# main.net
KiCad netlist of a schematic drawn in EAGLE
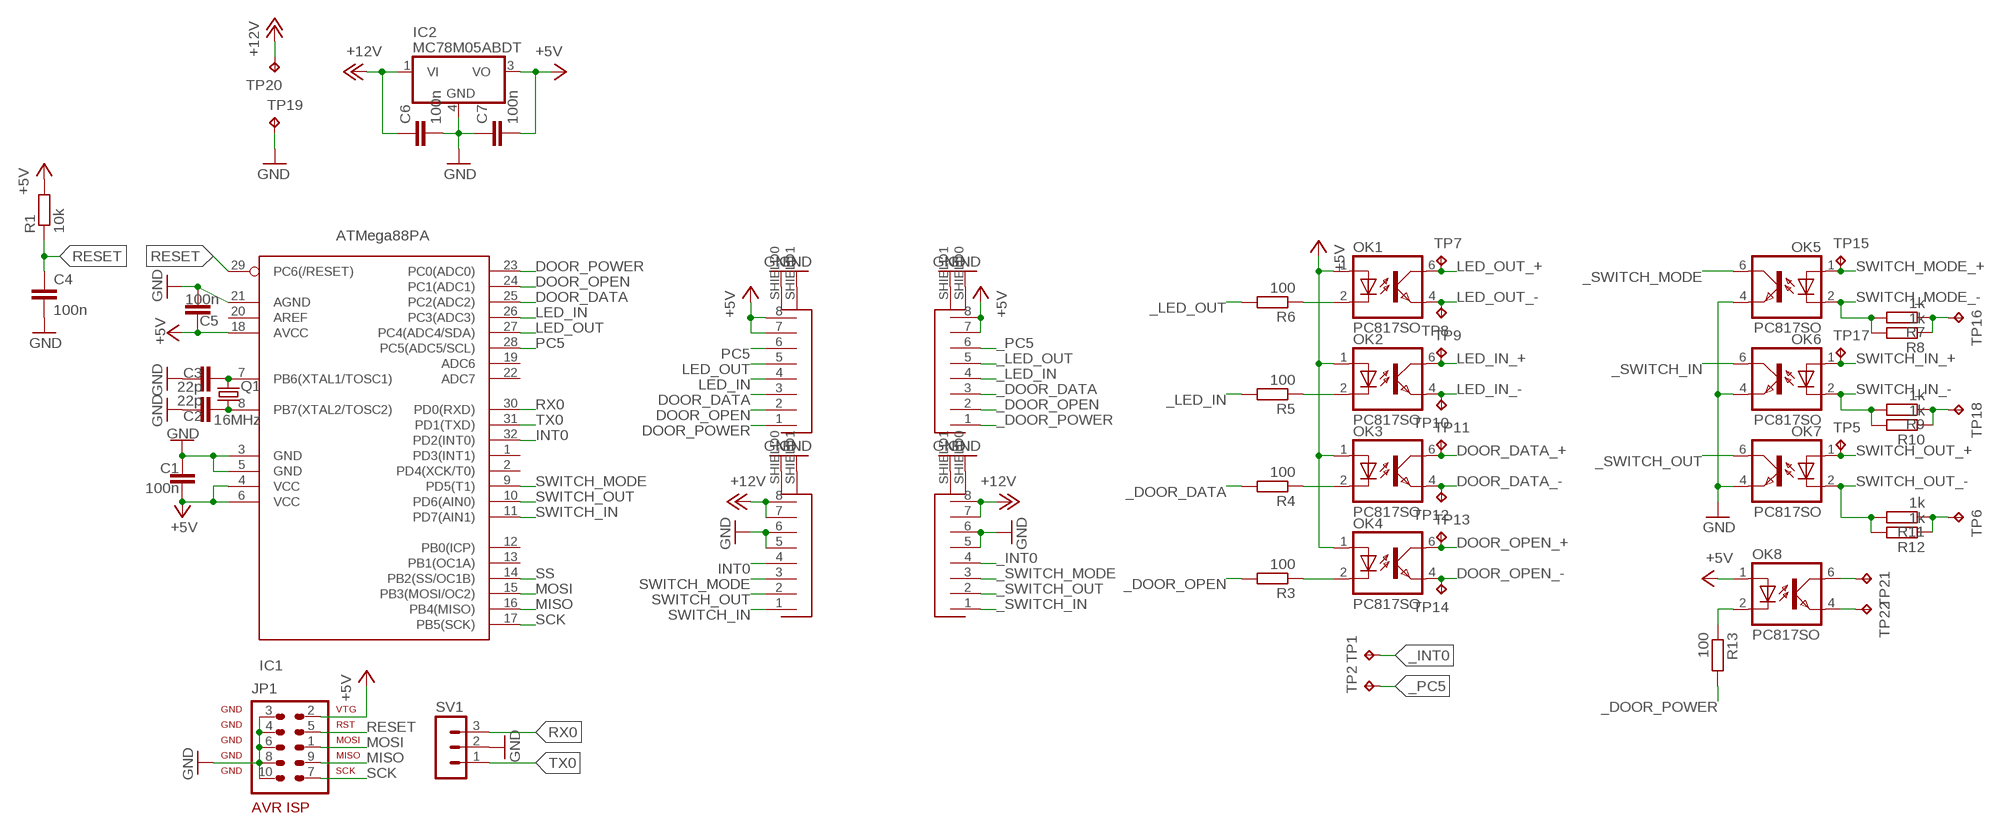
[diagram p0: schematic, sheet 1]

(export (version "E")
  (design (tool "Eeschema 10.0.6"))
  (components
    (comp (ref "C1")
      (value "100n")
      (footprint "eagle-import:C0805")
      (libsource (lib "eagle-import") (part "C-EUC0805"))
    )
    (comp (ref "C2")
      (value "22p")
      (footprint "eagle-import:C0805")
      (libsource (lib "eagle-import") (part "C-EUC0805"))
    )
    (comp (ref "C3")
      (value "22p")
      (footprint "eagle-import:C0805")
      (libsource (lib "eagle-import") (part "C-EUC0805"))
    )
    (comp (ref "C4")
      (value "100n")
      (footprint "eagle-import:C0805")
      (libsource (lib "eagle-import") (part "C-EUC0805"))
    )
    (comp (ref "C5")
      (value "100n")
      (footprint "eagle-import:C0805")
      (libsource (lib "eagle-import") (part "C-EUC0805"))
    )
    (comp (ref "C6")
      (value "100n")
      (footprint "eagle-import:C0805")
      (libsource (lib "eagle-import") (part "C-EUC0805"))
    )
    (comp (ref "C7")
      (value "100n")
      (footprint "eagle-import:C0805")
      (libsource (lib "eagle-import") (part "C-EUC0805"))
    )
    (comp (ref "CON1")
      (value "451000")
      (footprint "eagle-import:451000")
      (libsource (lib "eagle-import") (part "451000"))
    )
    (comp (ref "CON1_")
      (value "451000")
      (footprint "eagle-import:451000")
      (libsource (lib "eagle-import") (part "451000"))
    )
    (comp (ref "CON2")
      (value "451000")
      (footprint "eagle-import:451000")
      (libsource (lib "eagle-import") (part "451000"))
    )
    (comp (ref "CON2_")
      (value "451000")
      (footprint "eagle-import:451000")
      (libsource (lib "eagle-import") (part "451000"))
    )
    (comp (ref "IC1")
      (value "ATMega88PA")
      (footprint "eagle-import:TQFP32-08")
      (libsource (lib "eagle-import") (part "MEGA8-AI"))
    )
    (comp (ref "IC2")
      (value "MC78M05ABDT")
      (footprint "eagle-import:DPACK_3")
      (libsource (lib "eagle-import") (part "MC78M05ABDT"))
    )
    (comp (ref "JP1")
      (value "AVR-ISP-10")
      (footprint "eagle-import:AVR-ISP-10")
      (libsource (lib "eagle-import") (part "AVR-ISP-10"))
    )
    (comp (ref "OK1")
      (value "PC817SO")
      (footprint "eagle-import:SO4")
      (libsource (lib "eagle-import") (part "PC817SO"))
    )
    (comp (ref "OK2")
      (value "PC817SO")
      (footprint "eagle-import:SO4")
      (libsource (lib "eagle-import") (part "PC817SO"))
    )
    (comp (ref "OK3")
      (value "PC817SO")
      (footprint "eagle-import:SO4")
      (libsource (lib "eagle-import") (part "PC817SO"))
    )
    (comp (ref "OK4")
      (value "PC817SO")
      (footprint "eagle-import:SO4")
      (libsource (lib "eagle-import") (part "PC817SO"))
    )
    (comp (ref "OK5")
      (value "PC817SO")
      (footprint "eagle-import:SO4")
      (libsource (lib "eagle-import") (part "PC817SO"))
    )
    (comp (ref "OK6")
      (value "PC817SO")
      (footprint "eagle-import:SO4")
      (libsource (lib "eagle-import") (part "PC817SO"))
    )
    (comp (ref "OK7")
      (value "PC817SO")
      (footprint "eagle-import:SO4")
      (libsource (lib "eagle-import") (part "PC817SO"))
    )
    (comp (ref "OK8")
      (value "PC817SO")
      (footprint "eagle-import:SO4")
      (libsource (lib "eagle-import") (part "PC817SO"))
    )
    (comp (ref "Q1")
      (value "16MHz")
      (footprint "eagle-import:MQ")
      (libsource (lib "eagle-import") (part "CRYSTALMQ"))
    )
    (comp (ref "R1")
      (value "10k")
      (footprint "eagle-import:M0805")
      (libsource (lib "eagle-import") (part "R-EU_M0805"))
    )
    (comp (ref "R3")
      (value "100")
      (footprint "eagle-import:M0805")
      (libsource (lib "eagle-import") (part "R-EU_M0805"))
    )
    (comp (ref "R4")
      (value "100")
      (footprint "eagle-import:M0805")
      (libsource (lib "eagle-import") (part "R-EU_M0805"))
    )
    (comp (ref "R5")
      (value "100")
      (footprint "eagle-import:M0805")
      (libsource (lib "eagle-import") (part "R-EU_M0805"))
    )
    (comp (ref "R6")
      (value "100")
      (footprint "eagle-import:M0805")
      (libsource (lib "eagle-import") (part "R-EU_M0805"))
    )
    (comp (ref "R7")
      (value "1k")
      (footprint "eagle-import:M0805")
      (libsource (lib "eagle-import") (part "R-EU_M0805"))
    )
    (comp (ref "R8")
      (value "1k")
      (footprint "eagle-import:M0805")
      (libsource (lib "eagle-import") (part "R-EU_M0805"))
    )
    (comp (ref "R9")
      (value "1k")
      (footprint "eagle-import:M0805")
      (libsource (lib "eagle-import") (part "R-EU_M0805"))
    )
    (comp (ref "R10")
      (value "1k")
      (footprint "eagle-import:M0805")
      (libsource (lib "eagle-import") (part "R-EU_M0805"))
    )
    (comp (ref "R11")
      (value "1k")
      (footprint "eagle-import:M0805")
      (libsource (lib "eagle-import") (part "R-EU_M0805"))
    )
    (comp (ref "R12")
      (value "1k")
      (footprint "eagle-import:M0805")
      (libsource (lib "eagle-import") (part "R-EU_M0805"))
    )
    (comp (ref "R13")
      (value "100")
      (footprint "eagle-import:M0805")
      (libsource (lib "eagle-import") (part "R-EU_M0805"))
    )
    (comp (ref "SV1")
      (value "MA03-1")
      (footprint "eagle-import:MA03-1")
      (libsource (lib "eagle-import") (part "MA03-1"))
    )
    (comp (ref "TP1")
      (value "TPTP20SQ")
      (footprint "eagle-import:TP20SQ")
      (libsource (lib "eagle-import") (part "TPTP20SQ"))
    )
    (comp (ref "TP2")
      (value "TPTP20SQ")
      (footprint "eagle-import:TP20SQ")
      (libsource (lib "eagle-import") (part "TPTP20SQ"))
    )
    (comp (ref "TP5")
      (value "TPTP20SQ")
      (footprint "eagle-import:TP20SQ")
      (libsource (lib "eagle-import") (part "TPTP20SQ"))
    )
    (comp (ref "TP6")
      (value "TPTP20SQ")
      (footprint "eagle-import:TP20SQ")
      (libsource (lib "eagle-import") (part "TPTP20SQ"))
    )
    (comp (ref "TP7")
      (value "TPTP20SQ")
      (footprint "eagle-import:TP20SQ")
      (libsource (lib "eagle-import") (part "TPTP20SQ"))
    )
    (comp (ref "TP8")
      (value "TPTP20SQ")
      (footprint "eagle-import:TP20SQ")
      (libsource (lib "eagle-import") (part "TPTP20SQ"))
    )
    (comp (ref "TP9")
      (value "TPTP20SQ")
      (footprint "eagle-import:TP20SQ")
      (libsource (lib "eagle-import") (part "TPTP20SQ"))
    )
    (comp (ref "TP10")
      (value "TPTP20SQ")
      (footprint "eagle-import:TP20SQ")
      (libsource (lib "eagle-import") (part "TPTP20SQ"))
    )
    (comp (ref "TP11")
      (value "TPTP20SQ")
      (footprint "eagle-import:TP20SQ")
      (libsource (lib "eagle-import") (part "TPTP20SQ"))
    )
    (comp (ref "TP12")
      (value "TPTP20SQ")
      (footprint "eagle-import:TP20SQ")
      (libsource (lib "eagle-import") (part "TPTP20SQ"))
    )
    (comp (ref "TP13")
      (value "TPTP20SQ")
      (footprint "eagle-import:TP20SQ")
      (libsource (lib "eagle-import") (part "TPTP20SQ"))
    )
    (comp (ref "TP14")
      (value "TPTP20SQ")
      (footprint "eagle-import:TP20SQ")
      (libsource (lib "eagle-import") (part "TPTP20SQ"))
    )
    (comp (ref "TP15")
      (value "TPTP20SQ")
      (footprint "eagle-import:TP20SQ")
      (libsource (lib "eagle-import") (part "TPTP20SQ"))
    )
    (comp (ref "TP16")
      (value "TPTP20SQ")
      (footprint "eagle-import:TP20SQ")
      (libsource (lib "eagle-import") (part "TPTP20SQ"))
    )
    (comp (ref "TP17")
      (value "TPTP20SQ")
      (footprint "eagle-import:TP20SQ")
      (libsource (lib "eagle-import") (part "TPTP20SQ"))
    )
    (comp (ref "TP18")
      (value "TPTP20SQ")
      (footprint "eagle-import:TP20SQ")
      (libsource (lib "eagle-import") (part "TPTP20SQ"))
    )
    (comp (ref "TP19")
      (value "TPTP20SQ")
      (footprint "eagle-import:TP20SQ")
      (libsource (lib "eagle-import") (part "TPTP20SQ"))
    )
    (comp (ref "TP20")
      (value "TPTP20SQ")
      (footprint "eagle-import:TP20SQ")
      (libsource (lib "eagle-import") (part "TPTP20SQ"))
    )
    (comp (ref "TP21")
      (value "TPTP20SQ")
      (footprint "eagle-import:TP20SQ")
      (libsource (lib "eagle-import") (part "TPTP20SQ"))
    )
    (comp (ref "TP22")
      (value "TPTP20SQ")
      (footprint "eagle-import:TP20SQ")
      (libsource (lib "eagle-import") (part "TPTP20SQ"))
    )
  )
  (nets
    (net (code "1") (name "+5V") (class "Default")
      (node (ref "C1") (pin "1") (pinfunction "1_1") (pintype "passive"))
      (node (ref "C5") (pin "1") (pinfunction "1_1") (pintype "passive"))
      (node (ref "C7") (pin "2") (pinfunction "2_2") (pintype "passive"))
      (node (ref "CON2") (pin "7") (pinfunction "7_7") (pintype "bidirectional"))
      (node (ref "CON2") (pin "8") (pinfunction "8_8") (pintype "bidirectional"))
      (node (ref "CON2_") (pin "7") (pinfunction "7_7") (pintype "bidirectional"))
      (node (ref "CON2_") (pin "8") (pinfunction "8_8") (pintype "bidirectional"))
      (node (ref "IC1") (pin "18") (pinfunction "AVCC_18") (pintype "bidirectional"))
      (node (ref "IC1") (pin "4") (pinfunction "VCC_4") (pintype "bidirectional"))
      (node (ref "IC1") (pin "6") (pinfunction "VCC_6") (pintype "bidirectional"))
      (node (ref "IC2") (pin "3") (pinfunction "VO_3") (pintype "passive"))
      (node (ref "JP1") (pin "2") (pinfunction "2_2") (pintype "passive"))
      (node (ref "OK1") (pin "1") (pinfunction "A_1") (pintype "passive"))
      (node (ref "OK2") (pin "1") (pinfunction "A_1") (pintype "passive"))
      (node (ref "OK3") (pin "1") (pinfunction "A_1") (pintype "passive"))
      (node (ref "OK4") (pin "1") (pinfunction "A_1") (pintype "passive"))
      (node (ref "OK8") (pin "1") (pinfunction "A_1") (pintype "passive"))
      (node (ref "R1") (pin "2") (pinfunction "2_2") (pintype "passive"))
    )
    (net (code "2") (name "+12V") (class "Default")
      (node (ref "C6") (pin "1") (pinfunction "1_1") (pintype "passive"))
      (node (ref "CON1") (pin "7") (pinfunction "7_7") (pintype "bidirectional"))
      (node (ref "CON1") (pin "8") (pinfunction "8_8") (pintype "bidirectional"))
      (node (ref "CON1_") (pin "7") (pinfunction "7_7") (pintype "bidirectional"))
      (node (ref "CON1_") (pin "8") (pinfunction "8_8") (pintype "bidirectional"))
      (node (ref "IC2") (pin "1") (pinfunction "VI_1") (pintype "input"))
      (node (ref "TP20") (pin "TP") (pinfunction "TP_TP") (pintype "input"))
    )
    (net (code "3") (name "/DOOR_DATA") (class "Default")
      (node (ref "CON2") (pin "3") (pinfunction "3_3") (pintype "bidirectional"))
      (node (ref "IC1") (pin "25") (pinfunction "PC2(ADC2)_25") (pintype "bidirectional"))
    )
    (net (code "4") (name "/DOOR_DATA_+") (class "Default")
      (node (ref "OK3") (pin "6") (pinfunction "COL_6") (pintype "passive"))
      (node (ref "TP11") (pin "TP") (pinfunction "TP_TP") (pintype "input"))
    )
    (net (code "5") (name "/DOOR_DATA_-") (class "Default")
      (node (ref "OK3") (pin "4") (pinfunction "EMIT_4") (pintype "passive"))
      (node (ref "TP12") (pin "TP") (pinfunction "TP_TP") (pintype "input"))
    )
    (net (code "6") (name "/DOOR_OPEN") (class "Default")
      (node (ref "CON2") (pin "2") (pinfunction "2_2") (pintype "bidirectional"))
      (node (ref "IC1") (pin "24") (pinfunction "PC1(ADC1)_24") (pintype "bidirectional"))
    )
    (net (code "7") (name "/DOOR_OPEN_+") (class "Default")
      (node (ref "OK4") (pin "6") (pinfunction "COL_6") (pintype "passive"))
      (node (ref "TP13") (pin "TP") (pinfunction "TP_TP") (pintype "input"))
    )
    (net (code "8") (name "/DOOR_OPEN_-") (class "Default")
      (node (ref "OK4") (pin "4") (pinfunction "EMIT_4") (pintype "passive"))
      (node (ref "TP14") (pin "TP") (pinfunction "TP_TP") (pintype "input"))
    )
    (net (code "9") (name "/DOOR_POWER") (class "Default")
      (node (ref "CON2") (pin "1") (pinfunction "1_1") (pintype "bidirectional"))
      (node (ref "IC1") (pin "23") (pinfunction "PC0(ADC0)_23") (pintype "bidirectional"))
    )
    (net (code "10") (name "/INT0") (class "Default")
      (node (ref "CON1") (pin "4") (pinfunction "4_4") (pintype "bidirectional"))
      (node (ref "IC1") (pin "32") (pinfunction "PD2(INT0)_32") (pintype "bidirectional"))
    )
    (net (code "11") (name "/LED_IN") (class "Default")
      (node (ref "CON2") (pin "4") (pinfunction "4_4") (pintype "bidirectional"))
      (node (ref "IC1") (pin "26") (pinfunction "PC3(ADC3)_26") (pintype "bidirectional"))
    )
    (net (code "12") (name "/LED_IN_+") (class "Default")
      (node (ref "OK2") (pin "6") (pinfunction "COL_6") (pintype "passive"))
      (node (ref "TP9") (pin "TP") (pinfunction "TP_TP") (pintype "input"))
    )
    (net (code "13") (name "/LED_IN_-") (class "Default")
      (node (ref "OK2") (pin "4") (pinfunction "EMIT_4") (pintype "passive"))
      (node (ref "TP10") (pin "TP") (pinfunction "TP_TP") (pintype "input"))
    )
    (net (code "14") (name "/LED_OUT") (class "Default")
      (node (ref "CON2") (pin "5") (pinfunction "5_5") (pintype "bidirectional"))
      (node (ref "IC1") (pin "27") (pinfunction "PC4(ADC4/SDA)_27") (pintype "bidirectional"))
    )
    (net (code "15") (name "/LED_OUT_+") (class "Default")
      (node (ref "OK1") (pin "6") (pinfunction "COL_6") (pintype "passive"))
      (node (ref "TP7") (pin "TP") (pinfunction "TP_TP") (pintype "input"))
    )
    (net (code "16") (name "/LED_OUT_-") (class "Default")
      (node (ref "OK1") (pin "4") (pinfunction "EMIT_4") (pintype "passive"))
      (node (ref "TP8") (pin "TP") (pinfunction "TP_TP") (pintype "input"))
    )
    (net (code "17") (name "/MISO") (class "Default")
      (node (ref "IC1") (pin "16") (pinfunction "PB4(MISO)_16") (pintype "bidirectional"))
      (node (ref "JP1") (pin "9") (pinfunction "9_9") (pintype "passive"))
    )
    (net (code "18") (name "/MOSI") (class "Default")
      (node (ref "IC1") (pin "15") (pinfunction "PB3(MOSI/OC2)_15") (pintype "bidirectional"))
      (node (ref "JP1") (pin "1") (pinfunction "1_1") (pintype "passive"))
    )
    (net (code "19") (name "/PC5") (class "Default")
      (node (ref "CON2") (pin "6") (pinfunction "6_6") (pintype "bidirectional"))
      (node (ref "IC1") (pin "28") (pinfunction "PC5(ADC5/SCL)_28") (pintype "bidirectional"))
    )
    (net (code "20") (name "/SCK") (class "Default")
      (node (ref "IC1") (pin "17") (pinfunction "PB5(SCK)_17") (pintype "bidirectional"))
      (node (ref "JP1") (pin "7") (pinfunction "7_7") (pintype "passive"))
    )
    (net (code "21") (name "/SS") (class "Default")
      (node (ref "IC1") (pin "14") (pinfunction "PB2(SS/OC1B)_14") (pintype "bidirectional"))
    )
    (net (code "22") (name "/SWITCH_IN") (class "Default")
      (node (ref "CON1") (pin "1") (pinfunction "1_1") (pintype "bidirectional"))
      (node (ref "IC1") (pin "11") (pinfunction "PD7(AIN1)_11") (pintype "bidirectional"))
    )
    (net (code "23") (name "/SWITCH_IN_+") (class "Default")
      (node (ref "OK6") (pin "1") (pinfunction "A_1") (pintype "passive"))
      (node (ref "TP17") (pin "TP") (pinfunction "TP_TP") (pintype "input"))
    )
    (net (code "24") (name "/SWITCH_IN_-") (class "Default")
      (node (ref "OK6") (pin "2") (pinfunction "C_2") (pintype "passive"))
      (node (ref "R10") (pin "2") (pinfunction "2_2") (pintype "passive"))
      (node (ref "R9") (pin "2") (pinfunction "2_2") (pintype "passive"))
    )
    (net (code "25") (name "/SWITCH_MODE") (class "Default")
      (node (ref "CON1") (pin "3") (pinfunction "3_3") (pintype "bidirectional"))
      (node (ref "IC1") (pin "9") (pinfunction "PD5(T1)_9") (pintype "bidirectional"))
    )
    (net (code "26") (name "/SWITCH_MODE_+") (class "Default")
      (node (ref "OK5") (pin "1") (pinfunction "A_1") (pintype "passive"))
      (node (ref "TP15") (pin "TP") (pinfunction "TP_TP") (pintype "input"))
    )
    (net (code "27") (name "/SWITCH_MODE_-") (class "Default")
      (node (ref "OK5") (pin "2") (pinfunction "C_2") (pintype "passive"))
      (node (ref "R7") (pin "2") (pinfunction "2_2") (pintype "passive"))
      (node (ref "R8") (pin "2") (pinfunction "2_2") (pintype "passive"))
    )
    (net (code "28") (name "/SWITCH_OUT") (class "Default")
      (node (ref "CON1") (pin "2") (pinfunction "2_2") (pintype "bidirectional"))
      (node (ref "IC1") (pin "10") (pinfunction "PD6(AIN0)_10") (pintype "bidirectional"))
    )
    (net (code "29") (name "/SWITCH_OUT_+") (class "Default")
      (node (ref "OK7") (pin "1") (pinfunction "A_1") (pintype "passive"))
      (node (ref "TP5") (pin "TP") (pinfunction "TP_TP") (pintype "input"))
    )
    (net (code "30") (name "/SWITCH_OUT_-") (class "Default")
      (node (ref "OK7") (pin "2") (pinfunction "C_2") (pintype "passive"))
      (node (ref "R11") (pin "2") (pinfunction "2_2") (pintype "passive"))
      (node (ref "R12") (pin "2") (pinfunction "2_2") (pintype "passive"))
    )
    (net (code "31") (name "/_DOOR_DATA") (class "Default")
      (node (ref "CON2_") (pin "3") (pinfunction "3_3") (pintype "bidirectional"))
      (node (ref "R4") (pin "2") (pinfunction "2_2") (pintype "passive"))
    )
    (net (code "32") (name "/_DOOR_OPEN") (class "Default")
      (node (ref "CON2_") (pin "2") (pinfunction "2_2") (pintype "bidirectional"))
      (node (ref "R3") (pin "2") (pinfunction "2_2") (pintype "passive"))
    )
    (net (code "33") (name "/_DOOR_POWER") (class "Default")
      (node (ref "CON2_") (pin "1") (pinfunction "1_1") (pintype "bidirectional"))
      (node (ref "R13") (pin "2") (pinfunction "2_2") (pintype "passive"))
    )
    (net (code "34") (name "/_LED_IN") (class "Default")
      (node (ref "CON2_") (pin "4") (pinfunction "4_4") (pintype "bidirectional"))
      (node (ref "R5") (pin "2") (pinfunction "2_2") (pintype "passive"))
    )
    (net (code "35") (name "/_LED_OUT") (class "Default")
      (node (ref "CON2_") (pin "5") (pinfunction "5_5") (pintype "bidirectional"))
      (node (ref "R6") (pin "2") (pinfunction "2_2") (pintype "passive"))
    )
    (net (code "36") (name "/_SWITCH_IN") (class "Default")
      (node (ref "CON1_") (pin "1") (pinfunction "1_1") (pintype "bidirectional"))
      (node (ref "OK6") (pin "6") (pinfunction "COL_6") (pintype "passive"))
    )
    (net (code "37") (name "/_SWITCH_MODE") (class "Default")
      (node (ref "CON1_") (pin "3") (pinfunction "3_3") (pintype "bidirectional"))
      (node (ref "OK5") (pin "6") (pinfunction "COL_6") (pintype "passive"))
    )
    (net (code "38") (name "/_SWITCH_OUT") (class "Default")
      (node (ref "CON1_") (pin "2") (pinfunction "2_2") (pintype "bidirectional"))
      (node (ref "OK7") (pin "6") (pinfunction "COL_6") (pintype "passive"))
    )
    (net (code "39") (name "GND") (class "Default")
      (node (ref "C1") (pin "2") (pinfunction "2_2") (pintype "passive"))
      (node (ref "C2") (pin "1") (pinfunction "1_1") (pintype "passive"))
      (node (ref "C3") (pin "1") (pinfunction "1_1") (pintype "passive"))
      (node (ref "C4") (pin "2") (pinfunction "2_2") (pintype "passive"))
      (node (ref "C5") (pin "2") (pinfunction "2_2") (pintype "passive"))
      (node (ref "C6") (pin "2") (pinfunction "2_2") (pintype "passive"))
      (node (ref "C7") (pin "1") (pinfunction "1_1") (pintype "passive"))
      (node (ref "CON1") (pin "5") (pinfunction "5_5") (pintype "bidirectional"))
      (node (ref "CON1") (pin "6") (pinfunction "6_6") (pintype "bidirectional"))
      (node (ref "CON1") (pin "SHIELD0") (pinfunction "SHIELD0_SHIELD0") (pintype "bidirectional"))
      (node (ref "CON1") (pin "SHIELD1") (pinfunction "SHIELD1_SHIELD1") (pintype "bidirectional"))
      (node (ref "CON1_") (pin "5") (pinfunction "5_5") (pintype "bidirectional"))
      (node (ref "CON1_") (pin "6") (pinfunction "6_6") (pintype "bidirectional"))
      (node (ref "CON1_") (pin "SHIELD0") (pinfunction "SHIELD0_SHIELD0") (pintype "bidirectional"))
      (node (ref "CON1_") (pin "SHIELD1") (pinfunction "SHIELD1_SHIELD1") (pintype "bidirectional"))
      (node (ref "CON2") (pin "SHIELD0") (pinfunction "SHIELD0_SHIELD0") (pintype "bidirectional"))
      (node (ref "CON2") (pin "SHIELD1") (pinfunction "SHIELD1_SHIELD1") (pintype "bidirectional"))
      (node (ref "CON2_") (pin "SHIELD0") (pinfunction "SHIELD0_SHIELD0") (pintype "bidirectional"))
      (node (ref "CON2_") (pin "SHIELD1") (pinfunction "SHIELD1_SHIELD1") (pintype "bidirectional"))
      (node (ref "IC1") (pin "21") (pinfunction "AGND_21") (pintype "bidirectional"))
      (node (ref "IC1") (pin "3") (pinfunction "GND_3") (pintype "bidirectional"))
      (node (ref "IC1") (pin "5") (pinfunction "GND_5") (pintype "bidirectional"))
      (node (ref "IC2") (pin "4") (pinfunction "GND_4") (pintype "passive"))
      (node (ref "JP1") (pin "10") (pinfunction "10_10") (pintype "passive"))
      (node (ref "JP1") (pin "3") (pinfunction "3_3") (pintype "passive"))
      (node (ref "JP1") (pin "4") (pinfunction "4_4") (pintype "passive"))
      (node (ref "JP1") (pin "6") (pinfunction "6_6") (pintype "passive"))
      (node (ref "JP1") (pin "8") (pinfunction "8_8") (pintype "passive"))
      (node (ref "OK5") (pin "4") (pinfunction "EMIT_4") (pintype "passive"))
      (node (ref "OK6") (pin "4") (pinfunction "EMIT_4") (pintype "passive"))
      (node (ref "OK7") (pin "4") (pinfunction "EMIT_4") (pintype "passive"))
      (node (ref "SV1") (pin "2") (pinfunction "2_2") (pintype "passive"))
      (node (ref "TP19") (pin "TP") (pinfunction "TP_TP") (pintype "input"))
    )
    (net (code "40") (name "Net-(IC1-PB6(XTAL1{slash}TOSC1))") (class "Default")
      (node (ref "C3") (pin "2") (pinfunction "2_2") (pintype "passive"))
      (node (ref "IC1") (pin "7") (pinfunction "PB6(XTAL1/TOSC1)_7") (pintype "bidirectional"))
      (node (ref "Q1") (pin "P3") (pinfunction "2_P3") (pintype "passive"))
    )
    (net (code "41") (name "Net-(IC1-PB7(XTAL2{slash}TOSC2))") (class "Default")
      (node (ref "C2") (pin "2") (pinfunction "2_2") (pintype "passive"))
      (node (ref "IC1") (pin "8") (pinfunction "PB7(XTAL2/TOSC2)_8") (pintype "bidirectional"))
      (node (ref "Q1") (pin "P1") (pinfunction "1_P1") (pintype "passive"))
    )
    (net (code "42") (name "Net-(OK1-C)") (class "Default")
      (node (ref "OK1") (pin "2") (pinfunction "C_2") (pintype "passive"))
      (node (ref "R6") (pin "1") (pinfunction "1_1") (pintype "passive"))
    )
    (net (code "43") (name "Net-(OK2-C)") (class "Default")
      (node (ref "OK2") (pin "2") (pinfunction "C_2") (pintype "passive"))
      (node (ref "R5") (pin "1") (pinfunction "1_1") (pintype "passive"))
    )
    (net (code "44") (name "Net-(OK3-C)") (class "Default")
      (node (ref "OK3") (pin "2") (pinfunction "C_2") (pintype "passive"))
      (node (ref "R4") (pin "1") (pinfunction "1_1") (pintype "passive"))
    )
    (net (code "45") (name "Net-(OK4-C)") (class "Default")
      (node (ref "OK4") (pin "2") (pinfunction "C_2") (pintype "passive"))
      (node (ref "R3") (pin "1") (pinfunction "1_1") (pintype "passive"))
    )
    (net (code "46") (name "Net-(OK8-C)") (class "Default")
      (node (ref "OK8") (pin "2") (pinfunction "C_2") (pintype "passive"))
      (node (ref "R13") (pin "1") (pinfunction "1_1") (pintype "passive"))
    )
    (net (code "47") (name "Net-(OK8-COL)") (class "Default")
      (node (ref "OK8") (pin "6") (pinfunction "COL_6") (pintype "passive"))
      (node (ref "TP21") (pin "TP") (pinfunction "TP_TP") (pintype "input"))
    )
    (net (code "48") (name "Net-(OK8-EMIT)") (class "Default")
      (node (ref "OK8") (pin "4") (pinfunction "EMIT_4") (pintype "passive"))
      (node (ref "TP22") (pin "TP") (pinfunction "TP_TP") (pintype "input"))
    )
    (net (code "49") (name "Net-(R7-Pad1)") (class "Default")
      (node (ref "R7") (pin "1") (pinfunction "1_1") (pintype "passive"))
      (node (ref "R8") (pin "1") (pinfunction "1_1") (pintype "passive"))
      (node (ref "TP16") (pin "TP") (pinfunction "TP_TP") (pintype "input"))
    )
    (net (code "50") (name "Net-(R10-Pad1)") (class "Default")
      (node (ref "R10") (pin "1") (pinfunction "1_1") (pintype "passive"))
      (node (ref "R9") (pin "1") (pinfunction "1_1") (pintype "passive"))
      (node (ref "TP18") (pin "TP") (pinfunction "TP_TP") (pintype "input"))
    )
    (net (code "51") (name "Net-(R11-Pad1)") (class "Default")
      (node (ref "R11") (pin "1") (pinfunction "1_1") (pintype "passive"))
      (node (ref "R12") (pin "1") (pinfunction "1_1") (pintype "passive"))
      (node (ref "TP6") (pin "TP") (pinfunction "TP_TP") (pintype "input"))
    )
    (net (code "52") (name "RESET") (class "Default")
      (node (ref "C4") (pin "1") (pinfunction "1_1") (pintype "passive"))
      (node (ref "IC1") (pin "29") (pinfunction "PC6(/RESET)_29") (pintype "bidirectional"))
      (node (ref "JP1") (pin "5") (pinfunction "5_5") (pintype "passive"))
      (node (ref "R1") (pin "1") (pinfunction "1_1") (pintype "passive"))
    )
    (net (code "53") (name "RX0") (class "Default")
      (node (ref "IC1") (pin "30") (pinfunction "PD0(RXD)_30") (pintype "bidirectional"))
      (node (ref "SV1") (pin "3") (pinfunction "3_3") (pintype "passive"))
    )
    (net (code "54") (name "TX0") (class "Default")
      (node (ref "IC1") (pin "31") (pinfunction "PD1(TXD)_31") (pintype "bidirectional"))
      (node (ref "SV1") (pin "1") (pinfunction "1_1") (pintype "passive"))
    )
    (net (code "55") (name "_INT0") (class "Default")
      (node (ref "CON1_") (pin "4") (pinfunction "4_4") (pintype "bidirectional"))
      (node (ref "TP1") (pin "TP") (pinfunction "TP_TP") (pintype "input"))
    )
    (net (code "56") (name "_PC5") (class "Default")
      (node (ref "CON2_") (pin "6") (pinfunction "6_6") (pintype "bidirectional"))
      (node (ref "TP2") (pin "TP") (pinfunction "TP_TP") (pintype "input"))
    )
    (net (code "57") (name "unconnected-(IC1-ADC6-Pad19)") (class "Default")
      (node (ref "IC1") (pin "19") (pinfunction "ADC6_19") (pintype "bidirectional"))
    )
    (net (code "58") (name "unconnected-(IC1-ADC7-Pad22)") (class "Default")
      (node (ref "IC1") (pin "22") (pinfunction "ADC7_22") (pintype "bidirectional"))
    )
    (net (code "59") (name "unconnected-(IC1-AREF-Pad20)") (class "Default")
      (node (ref "IC1") (pin "20") (pinfunction "AREF_20") (pintype "bidirectional"))
    )
    (net (code "60") (name "unconnected-(IC1-PB0(ICP)-Pad12)") (class "Default")
      (node (ref "IC1") (pin "12") (pinfunction "PB0(ICP)_12") (pintype "bidirectional"))
    )
    (net (code "61") (name "unconnected-(IC1-PB1(OC1A)-Pad13)") (class "Default")
      (node (ref "IC1") (pin "13") (pinfunction "PB1(OC1A)_13") (pintype "bidirectional"))
    )
    (net (code "62") (name "unconnected-(IC1-PD3(INT1)-Pad1)") (class "Default")
      (node (ref "IC1") (pin "1") (pinfunction "PD3(INT1)_1") (pintype "bidirectional"))
    )
    (net (code "63") (name "unconnected-(IC1-PD4(XCK{slash}T0)-Pad2)") (class "Default")
      (node (ref "IC1") (pin "2") (pinfunction "PD4(XCK/T0)_2") (pintype "bidirectional"))
    )
  )
)
